# 1-Schematic_LED_Bargraph_Driver_PCB.net
KiCad netlist of a schematic drawn in EasyEDA
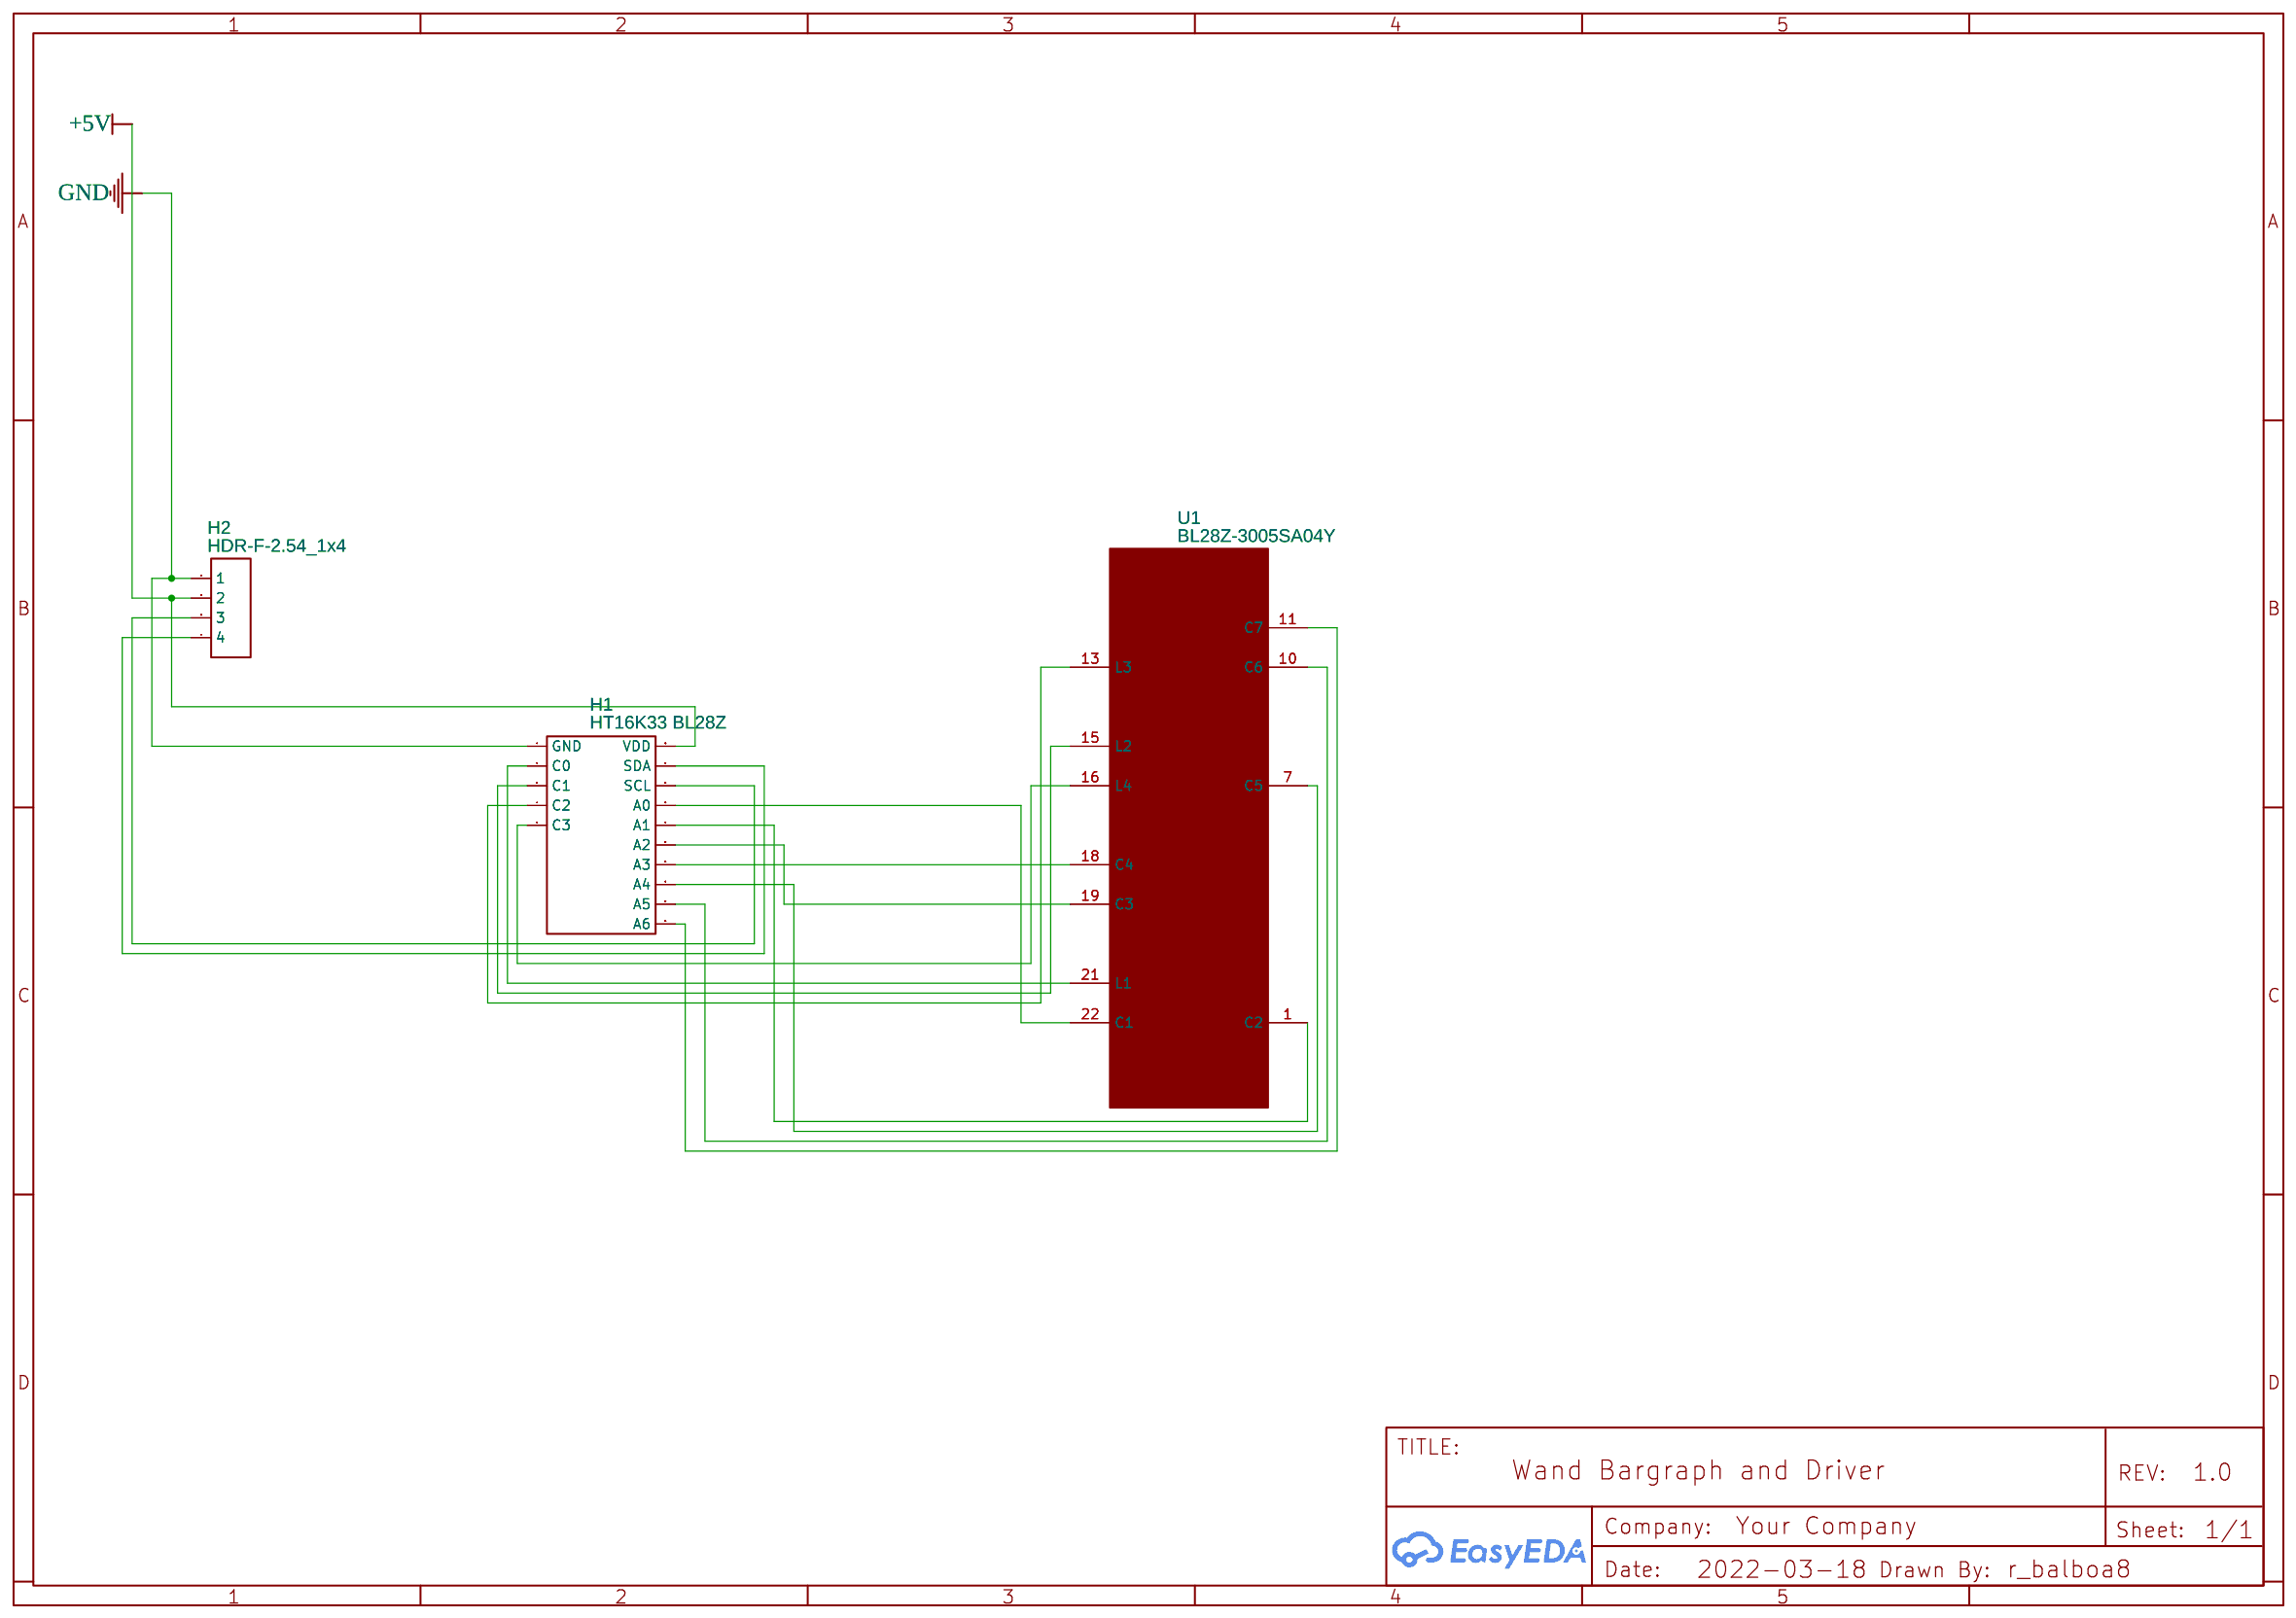
[diagram p0: schematic sheet]

(export (version "E")
  (design (tool "Eeschema 10.0.6"))
  (components
    (comp (ref "H1")
      (value "HT16K33 BL28Z")
      (fields (field (name "BOM_Supplier Part") "C225505"))
      (libsource (lib "") (part "HT16K33 BL28Z"))
    )
    (comp (ref "H2")
      (value "HDR-F-2.54_1x4")
      (fields (field (name "BOM_Supplier Part") "C225501"))
      (libsource (lib "") (part "HDR-F-2.54_1x4"))
    )
    (comp (ref "U1")
      (value "BL28Z-3005SA04Y")
      (fields (field (name "BOM_Manufacturer Part") "BL28-3005SDK04"))
      (libsource (lib "") (part "BL28Z-3005SA04Y"))
    )
  )
  (nets
    (net (code "1") (name "+5V") (class "Default")
      (node (ref "H1") (pin "28") (pinfunction "VDD_28") (pintype "unspecified"))
      (node (ref "H2") (pin "2") (pinfunction "2_2") (pintype "unspecified"))
    )
    (net (code "2") (name "GND") (class "Default")
      (node (ref "H1") (pin "1") (pinfunction "GND_1") (pintype "unspecified"))
      (node (ref "H2") (pin "1") (pinfunction "1_1") (pintype "unspecified"))
    )
    (net (code "3") (name "Net-(H1-A0)") (class "Default")
      (node (ref "H1") (pin "25") (pinfunction "A0_25") (pintype "unspecified"))
      (node (ref "U1") (pin "22") (pinfunction "C1_22") (pintype "unspecified"))
    )
    (net (code "4") (name "Net-(H1-A1)") (class "Default")
      (node (ref "H1") (pin "24") (pinfunction "A1_24") (pintype "unspecified"))
      (node (ref "U1") (pin "1") (pinfunction "C2_1") (pintype "unspecified"))
    )
    (net (code "5") (name "Net-(H1-A2)") (class "Default")
      (node (ref "H1") (pin "23") (pinfunction "A2_23") (pintype "unspecified"))
      (node (ref "U1") (pin "19") (pinfunction "C3_19") (pintype "unspecified"))
    )
    (net (code "6") (name "Net-(H1-A3)") (class "Default")
      (node (ref "H1") (pin "22") (pinfunction "A3_22") (pintype "unspecified"))
      (node (ref "U1") (pin "18") (pinfunction "C4_18") (pintype "unspecified"))
    )
    (net (code "7") (name "Net-(H1-A4)") (class "Default")
      (node (ref "H1") (pin "21") (pinfunction "A4_21") (pintype "unspecified"))
      (node (ref "U1") (pin "7") (pinfunction "C5_7") (pintype "unspecified"))
    )
    (net (code "8") (name "Net-(H1-A5)") (class "Default")
      (node (ref "H1") (pin "20") (pinfunction "A5_20") (pintype "unspecified"))
      (node (ref "U1") (pin "10") (pinfunction "C6_10") (pintype "unspecified"))
    )
    (net (code "9") (name "Net-(H1-A6)") (class "Default")
      (node (ref "H1") (pin "19") (pinfunction "A6_19") (pintype "unspecified"))
      (node (ref "U1") (pin "11") (pinfunction "C7_11") (pintype "unspecified"))
    )
    (net (code "10") (name "Net-(H1-C0)") (class "Default")
      (node (ref "H1") (pin "2") (pinfunction "C0_2") (pintype "unspecified"))
      (node (ref "U1") (pin "21") (pinfunction "L1_21") (pintype "unspecified"))
    )
    (net (code "11") (name "Net-(H1-C1)") (class "Default")
      (node (ref "H1") (pin "3") (pinfunction "C1_3") (pintype "unspecified"))
      (node (ref "U1") (pin "15") (pinfunction "L2_15") (pintype "unspecified"))
    )
    (net (code "12") (name "Net-(H1-C2)") (class "Default")
      (node (ref "H1") (pin "4") (pinfunction "C2_4") (pintype "unspecified"))
      (node (ref "U1") (pin "13") (pinfunction "L3_13") (pintype "unspecified"))
    )
    (net (code "13") (name "Net-(H1-C3)") (class "Default")
      (node (ref "H1") (pin "5") (pinfunction "C3_5") (pintype "unspecified"))
      (node (ref "U1") (pin "16") (pinfunction "L4_16") (pintype "unspecified"))
    )
    (net (code "14") (name "Net-(H1-SCL)") (class "Default")
      (node (ref "H1") (pin "26") (pinfunction "SCL_26") (pintype "unspecified"))
      (node (ref "H2") (pin "3") (pinfunction "3_3") (pintype "unspecified"))
    )
    (net (code "15") (name "Net-(H1-SDA)") (class "Default")
      (node (ref "H1") (pin "27") (pinfunction "SDA_27") (pintype "unspecified"))
      (node (ref "H2") (pin "4") (pinfunction "4_4") (pintype "unspecified"))
    )
  )
)
